# mini.net
KiCad netlist of a schematic drawn in Altium Designer
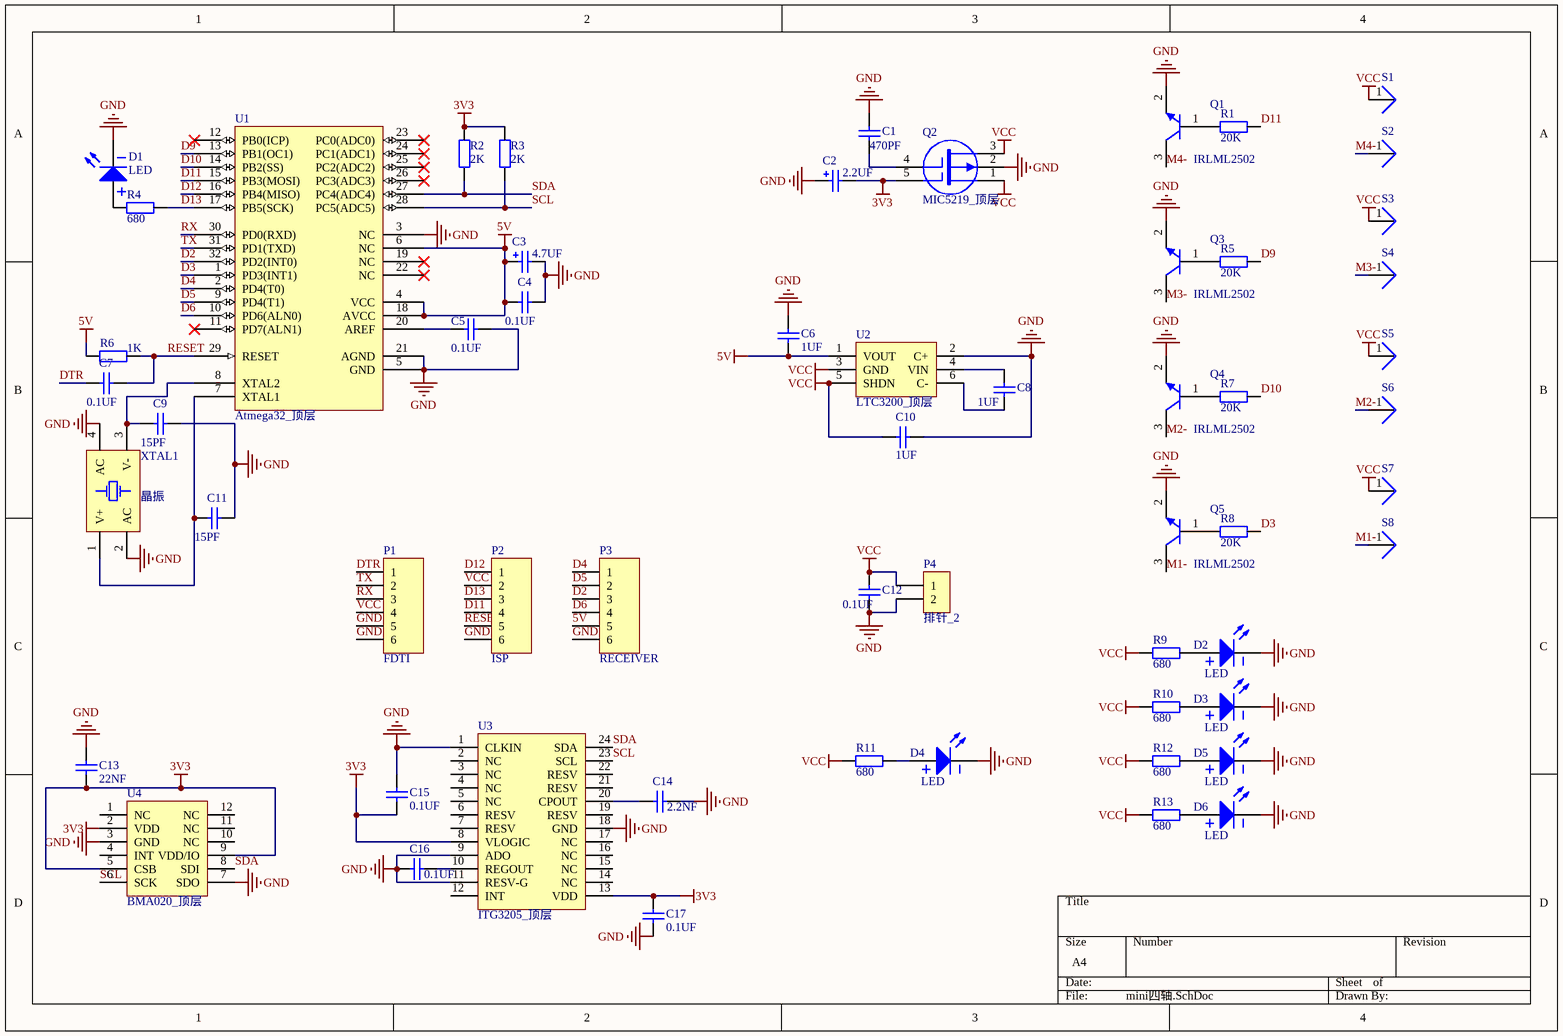
[diagram p0: mini四轴.SchDoc]

(export (version "E")
  (design (tool "Eeschema 10.0.6"))
  (components
    (comp (ref "C1")
      (value "470PF")
      (footprint "0805_顶层")
      (description "电容")
      (libsource (lib "贴片库") (part "电容_无极性_0805_顶层"))
    )
    (comp (ref "C2")
      (value "2.2UF")
      (footprint "A型电容")
      (description "电容_A型")
      (libsource (lib "贴片库") (part "电容_A型"))
    )
    (comp (ref "C3")
      (value "4.7UF")
      (footprint "A型电容")
      (description "电容_A型")
      (libsource (lib "贴片库") (part "电容_A型"))
    )
    (comp (ref "C4")
      (value "0.1UF")
      (footprint "0805_顶层")
      (description "电容")
      (libsource (lib "贴片库") (part "电容_无极性_0805_顶层"))
    )
    (comp (ref "C5")
      (value "0.1UF")
      (footprint "0805_顶层")
      (description "电容")
      (libsource (lib "贴片库") (part "电容_无极性_0805_顶层"))
    )
    (comp (ref "C6")
      (value "1UF")
      (footprint "0805_顶层")
      (description "电容")
      (libsource (lib "贴片库") (part "电容_无极性_0805_顶层"))
    )
    (comp (ref "C7")
      (value "0.1UF")
      (footprint "0805_顶层")
      (description "电容")
      (libsource (lib "贴片库") (part "电容_无极性_0805_顶层"))
    )
    (comp (ref "C8")
      (value "1UF")
      (footprint "0805_顶层")
      (description "电容")
      (libsource (lib "贴片库") (part "电容_无极性_0805_顶层"))
    )
    (comp (ref "C9")
      (value "15PF")
      (footprint "0805_顶层")
      (description "电容")
      (libsource (lib "贴片库") (part "电容_无极性_0805_顶层"))
    )
    (comp (ref "C10")
      (value "1UF")
      (footprint "0805_顶层")
      (description "电容")
      (libsource (lib "贴片库") (part "电容_无极性_0805_顶层"))
    )
    (comp (ref "C11")
      (value "15PF")
      (footprint "0805_顶层")
      (description "电容")
      (libsource (lib "贴片库") (part "电容_无极性_0805_顶层"))
    )
    (comp (ref "C12")
      (value "0.1UF")
      (footprint "0805_顶层")
      (description "电容")
      (libsource (lib "贴片库") (part "电容_无极性_0805_顶层"))
    )
    (comp (ref "C13")
      (value "22NF")
      (footprint "0805_顶层")
      (description "电容")
      (libsource (lib "贴片库") (part "电容_无极性_0805_顶层"))
    )
    (comp (ref "C14")
      (value "2.2NF")
      (footprint "0805_顶层")
      (description "电容")
      (libsource (lib "贴片库") (part "电容_无极性_0805_顶层"))
    )
    (comp (ref "C15")
      (value "0.1UF")
      (footprint "0805_顶层")
      (description "电容")
      (libsource (lib "贴片库") (part "电容_无极性_0805_顶层"))
    )
    (comp (ref "C16")
      (value "0.1UF")
      (footprint "0805_顶层")
      (description "电容")
      (libsource (lib "贴片库") (part "电容_无极性_0805_顶层"))
    )
    (comp (ref "C17")
      (value "0.1UF")
      (footprint "0805_顶层")
      (description "电容")
      (libsource (lib "贴片库") (part "电容_无极性_0805_顶层"))
    )
    (comp (ref "D1") (value "LED") (footprint "0805_顶层") (libsource (lib "贴片库") (part "LED_0805_顶层")))
    (comp (ref "D2") (value "LED") (footprint "0805_顶层") (libsource (lib "贴片库") (part "LED_0805_顶层")))
    (comp (ref "D3") (value "LED") (footprint "0805_顶层") (libsource (lib "贴片库") (part "LED_0805_顶层")))
    (comp (ref "D4") (value "LED") (footprint "0805_顶层") (libsource (lib "贴片库") (part "LED_0805_顶层")))
    (comp (ref "D5") (value "LED") (footprint "0805_顶层") (libsource (lib "贴片库") (part "LED_0805_顶层")))
    (comp (ref "D6") (value "LED") (footprint "0805_顶层") (libsource (lib "贴片库") (part "LED_0805_顶层")))
    (comp (ref "P1")
      (value "FDTI")
      (footprint "排针_6_2.54")
      (description "排针_6_2.54")
      (libsource (lib "贴片库") (part "排针_6_2.54"))
    )
    (comp (ref "P2")
      (value "ISP")
      (footprint "排针_6_2.54")
      (description "排针_6_2.54")
      (libsource (lib "贴片库") (part "排针_6_2.54"))
    )
    (comp (ref "P3")
      (value "RECEIVER")
      (footprint "排针_6_2.54")
      (description "排针_6_2.54")
      (libsource (lib "贴片库") (part "排针_6_2.54"))
    )
    (comp (ref "P4") (value "排针_2") (footprint "排针_2") (libsource (lib "贴片库") (part "排针_2")))
    (comp (ref "Q1")
      (value "IRLML2502")
      (footprint "IRLML2502_顶层")
      (libsource (lib "贴片库") (part "IRLML2502_顶层"))
    )
    (comp (ref "Q2")
      (value "MIC5219_顶层")
      (footprint "MIC5219_顶层")
      (description "MIC5219")
      (libsource (lib "贴片库") (part "MIC5219_顶层"))
    )
    (comp (ref "Q3")
      (value "IRLML2502")
      (footprint "IRLML2502_顶层")
      (libsource (lib "贴片库") (part "IRLML2502_顶层"))
    )
    (comp (ref "Q4")
      (value "IRLML2502")
      (footprint "IRLML2502_顶层")
      (libsource (lib "贴片库") (part "IRLML2502_顶层"))
    )
    (comp (ref "Q5")
      (value "IRLML2502")
      (footprint "IRLML2502_顶层")
      (libsource (lib "贴片库") (part "IRLML2502_顶层"))
    )
    (comp (ref "R1")
      (value "20K")
      (footprint "0805_顶层")
      (description "电阻")
      (libsource (lib "贴片库") (part "电阻_0805_顶层"))
    )
    (comp (ref "R2")
      (value "2K")
      (footprint "0805_顶层")
      (description "电阻")
      (libsource (lib "") (part "电阻_0805_顶层_1"))
    )
    (comp (ref "R3")
      (value "2K")
      (footprint "0805_顶层")
      (description "电阻")
      (libsource (lib "") (part "电阻_0805_顶层_1"))
    )
    (comp (ref "R4")
      (value "680")
      (footprint "0805_顶层")
      (description "电阻")
      (libsource (lib "贴片库") (part "电阻_0805_顶层"))
    )
    (comp (ref "R5")
      (value "20K")
      (footprint "0805_顶层")
      (description "电阻")
      (libsource (lib "贴片库") (part "电阻_0805_顶层"))
    )
    (comp (ref "R6")
      (value "1K")
      (footprint "0805_顶层")
      (description "电阻")
      (libsource (lib "贴片库") (part "电阻_0805_顶层"))
    )
    (comp (ref "R7")
      (value "20K")
      (footprint "0805_顶层")
      (description "电阻")
      (libsource (lib "贴片库") (part "电阻_0805_顶层"))
    )
    (comp (ref "R8")
      (value "20K")
      (footprint "0805_顶层")
      (description "电阻")
      (libsource (lib "贴片库") (part "电阻_0805_顶层"))
    )
    (comp (ref "R9")
      (value "680")
      (footprint "0805_顶层")
      (description "电阻")
      (libsource (lib "贴片库") (part "电阻_0805_顶层"))
    )
    (comp (ref "R10")
      (value "680")
      (footprint "0805_顶层")
      (description "电阻")
      (libsource (lib "贴片库") (part "电阻_0805_顶层"))
    )
    (comp (ref "R11")
      (value "680")
      (footprint "0805_顶层")
      (description "电阻")
      (libsource (lib "贴片库") (part "电阻_0805_顶层"))
    )
    (comp (ref "R12")
      (value "680")
      (footprint "0805_顶层")
      (description "电阻")
      (libsource (lib "贴片库") (part "电阻_0805_顶层"))
    )
    (comp (ref "R13")
      (value "680")
      (footprint "0805_顶层")
      (description "电阻")
      (libsource (lib "贴片库") (part "电阻_0805_顶层"))
    )
    (comp (ref "S1")
      (value "~")
      (footprint "焊盘_顶层")
      (description "焊盘")
      (libsource (lib "贴片库") (part "焊盘_顶层"))
    )
    (comp (ref "S2")
      (value "~")
      (footprint "焊盘_顶层")
      (description "焊盘")
      (libsource (lib "贴片库") (part "焊盘_顶层"))
    )
    (comp (ref "S3")
      (value "~")
      (footprint "焊盘_顶层")
      (description "焊盘")
      (libsource (lib "贴片库") (part "焊盘_顶层"))
    )
    (comp (ref "S4")
      (value "~")
      (footprint "焊盘_顶层")
      (description "焊盘")
      (libsource (lib "贴片库") (part "焊盘_顶层"))
    )
    (comp (ref "S5")
      (value "~")
      (footprint "焊盘_顶层")
      (description "焊盘")
      (libsource (lib "贴片库") (part "焊盘_顶层"))
    )
    (comp (ref "S6")
      (value "~")
      (footprint "焊盘_顶层")
      (description "焊盘")
      (libsource (lib "贴片库") (part "焊盘_顶层"))
    )
    (comp (ref "S7")
      (value "~")
      (footprint "焊盘_顶层")
      (description "焊盘")
      (libsource (lib "贴片库") (part "焊盘_顶层"))
    )
    (comp (ref "S8")
      (value "~")
      (footprint "焊盘_顶层")
      (description "焊盘")
      (libsource (lib "贴片库") (part "焊盘_顶层"))
    )
    (comp (ref "U1")
      (value "Atmega32_顶层")
      (footprint "Atmega32_顶层")
      (description "Atmega32")
      (libsource (lib "贴片库") (part "Atmega32_顶层"))
    )
    (comp (ref "U2")
      (value "LTC3200_顶层")
      (footprint "LTC3200_顶层")
      (description "LTC3200")
      (libsource (lib "贴片库") (part "LTC3200_顶层"))
    )
    (comp (ref "U3")
      (value "ITG3205_顶层")
      (footprint "ITG3205_顶层")
      (description "ITG3205")
      (libsource (lib "贴片库") (part "ITG3205_顶层"))
    )
    (comp (ref "U4")
      (value "BMA020_顶层")
      (footprint "BMA020_顶层")
      (description "BMA020")
      (libsource (lib "贴片库") (part "BMA020_顶层"))
    )
    (comp (ref "XTAL1") (value "晶振") (footprint "晶振_3225_顶层") (libsource (lib "贴片库") (part "晶振_3225_顶层")))
  )
  (nets
    (net (code "1") (name "/D2") (class "Default")
      (node (ref "P3") (pin "3") (pinfunction "3_3") (pintype "passive"))
      (node (ref "U1") (pin "32") (pinfunction "PD2(INT0)_32") (pintype "bidirectional"))
    )
    (net (code "2") (name "/D3") (class "Default")
      (node (ref "R8") (pin "1") (pinfunction "1_1") (pintype "passive"))
      (node (ref "U1") (pin "1") (pinfunction "PD3(INT1)_1") (pintype "bidirectional"))
    )
    (net (code "3") (name "/D4") (class "Default")
      (node (ref "P3") (pin "1") (pinfunction "1_1") (pintype "passive"))
      (node (ref "U1") (pin "2") (pinfunction "PD4(T0)_2") (pintype "bidirectional"))
    )
    (net (code "4") (name "/D5") (class "Default")
      (node (ref "P3") (pin "2") (pinfunction "2_2") (pintype "passive"))
      (node (ref "U1") (pin "9") (pinfunction "PD4(T1)_9") (pintype "bidirectional"))
    )
    (net (code "5") (name "/D6") (class "Default")
      (node (ref "P3") (pin "4") (pinfunction "4_4") (pintype "passive"))
      (node (ref "U1") (pin "10") (pinfunction "PD6(ALN0)_10") (pintype "bidirectional"))
    )
    (net (code "6") (name "/D9") (class "Default")
      (node (ref "R5") (pin "1") (pinfunction "1_1") (pintype "passive"))
      (node (ref "U1") (pin "13") (pinfunction "PB1(OC1)_13") (pintype "bidirectional"))
    )
    (net (code "7") (name "/D10") (class "Default")
      (node (ref "R7") (pin "1") (pinfunction "1_1") (pintype "passive"))
      (node (ref "U1") (pin "14") (pinfunction "PB2(SS)_14") (pintype "bidirectional"))
    )
    (net (code "8") (name "/D11") (class "Default")
      (node (ref "P2") (pin "4") (pinfunction "4_4") (pintype "passive"))
      (node (ref "R1") (pin "1") (pinfunction "1_1") (pintype "passive"))
      (node (ref "U1") (pin "15") (pinfunction "PB3(MOSI)_15") (pintype "bidirectional"))
    )
    (net (code "9") (name "/D12") (class "Default")
      (node (ref "P2") (pin "1") (pinfunction "1_1") (pintype "passive"))
      (node (ref "U1") (pin "16") (pinfunction "PB4(MISO)_16") (pintype "bidirectional"))
    )
    (net (code "10") (name "/D13") (class "Default")
      (node (ref "P2") (pin "3") (pinfunction "3_3") (pintype "passive"))
      (node (ref "R4") (pin "1") (pinfunction "1_1") (pintype "passive"))
      (node (ref "U1") (pin "17") (pinfunction "PB5(SCK)_17") (pintype "bidirectional"))
    )
    (net (code "11") (name "/DTR") (class "Default")
      (node (ref "C7") (pin "1") (pinfunction "1_1") (pintype "passive"))
      (node (ref "P1") (pin "1") (pinfunction "1_1") (pintype "passive"))
    )
    (net (code "12") (name "/M1-") (class "Default")
      (node (ref "Q5") (pin "3") (pinfunction "3_3") (pintype "passive"))
      (node (ref "S8") (pin "1") (pinfunction "1_1") (pintype "passive"))
    )
    (net (code "13") (name "/M2-") (class "Default")
      (node (ref "Q4") (pin "3") (pinfunction "3_3") (pintype "passive"))
      (node (ref "S6") (pin "1") (pinfunction "1_1") (pintype "passive"))
    )
    (net (code "14") (name "/M3-") (class "Default")
      (node (ref "Q3") (pin "3") (pinfunction "3_3") (pintype "passive"))
      (node (ref "S4") (pin "1") (pinfunction "1_1") (pintype "passive"))
    )
    (net (code "15") (name "/M4-") (class "Default")
      (node (ref "Q1") (pin "3") (pinfunction "3_3") (pintype "passive"))
      (node (ref "S2") (pin "1") (pinfunction "1_1") (pintype "passive"))
    )
    (net (code "16") (name "/RESET") (class "Default")
      (node (ref "C7") (pin "2") (pinfunction "2_2") (pintype "passive"))
      (node (ref "P2") (pin "5") (pinfunction "5_5") (pintype "passive"))
      (node (ref "R6") (pin "1") (pinfunction "1_1") (pintype "passive"))
      (node (ref "U1") (pin "29") (pinfunction "RESET_29") (pintype "input"))
    )
    (net (code "17") (name "/RX") (class "Default")
      (node (ref "P1") (pin "3") (pinfunction "3_3") (pintype "passive"))
      (node (ref "U1") (pin "30") (pinfunction "PD0(RXD)_30") (pintype "bidirectional"))
    )
    (net (code "18") (name "/SCL") (class "Default")
      (node (ref "R3") (pin "2") (pinfunction "2_2") (pintype "passive"))
      (node (ref "U1") (pin "28") (pinfunction "PC5(ADC5)_28") (pintype "bidirectional"))
      (node (ref "U3") (pin "23") (pinfunction "SCL_23") (pintype "passive"))
      (node (ref "U4") (pin "6") (pinfunction "SCK_6") (pintype "passive"))
    )
    (net (code "19") (name "/SDA") (class "Default")
      (node (ref "R2") (pin "2") (pinfunction "2_2") (pintype "passive"))
      (node (ref "U1") (pin "27") (pinfunction "PC4(ADC4)_27") (pintype "bidirectional"))
      (node (ref "U3") (pin "24") (pinfunction "SDA_24") (pintype "passive"))
      (node (ref "U4") (pin "8") (pinfunction "SDI_8") (pintype "passive"))
    )
    (net (code "20") (name "/TX") (class "Default")
      (node (ref "P1") (pin "2") (pinfunction "2_2") (pintype "passive"))
      (node (ref "U1") (pin "31") (pinfunction "PD1(TXD)_31") (pintype "bidirectional"))
    )
    (net (code "21") (name "3V3") (class "Default")
      (node (ref "C13") (pin "1") (pinfunction "1_1") (pintype "passive"))
      (node (ref "C15") (pin "1") (pinfunction "1_1") (pintype "passive"))
      (node (ref "C17") (pin "2") (pinfunction "2_2") (pintype "passive"))
      (node (ref "C2") (pin "2") (pinfunction "2_2") (pintype "passive"))
      (node (ref "Q2") (pin "5") (pinfunction "5_5") (pintype "passive"))
      (node (ref "R2") (pin "1") (pinfunction "1_1") (pintype "passive"))
      (node (ref "R3") (pin "1") (pinfunction "1_1") (pintype "passive"))
      (node (ref "U3") (pin "13") (pinfunction "VDD_13") (pintype "passive"))
      (node (ref "U3") (pin "8") (pinfunction "VLOGIC_8") (pintype "passive"))
      (node (ref "U4") (pin "2") (pinfunction "VDD_2") (pintype "passive"))
      (node (ref "U4") (pin "5") (pinfunction "CSB_5") (pintype "passive"))
      (node (ref "U4") (pin "9") (pinfunction "VDD/IO_9") (pintype "passive"))
    )
    (net (code "22") (name "5V") (class "Default")
      (node (ref "C3") (pin "1") (pinfunction "1_1") (pintype "passive"))
      (node (ref "C4") (pin "1") (pinfunction "1_1") (pintype "passive"))
      (node (ref "C6") (pin "1") (pinfunction "1_1") (pintype "passive"))
      (node (ref "P3") (pin "5") (pinfunction "5_5") (pintype "passive"))
      (node (ref "R6") (pin "2") (pinfunction "2_2") (pintype "passive"))
      (node (ref "U1") (pin "18") (pinfunction "AVCC_18") (pintype "passive"))
      (node (ref "U1") (pin "4") (pinfunction "VCC_4") (pintype "passive"))
      (node (ref "U1") (pin "6") (pinfunction "NC_6") (pintype "passive"))
      (node (ref "U2") (pin "1") (pinfunction "VOUT_1") (pintype "passive"))
    )
    (net (code "23") (name "GND") (class "Default")
      (node (ref "C1") (pin "2") (pinfunction "2_2") (pintype "passive"))
      (node (ref "C10") (pin "1") (pinfunction "1_1") (pintype "passive"))
      (node (ref "C11") (pin "2") (pinfunction "2_2") (pintype "passive"))
      (node (ref "C12") (pin "1") (pinfunction "1_1") (pintype "passive"))
      (node (ref "C13") (pin "2") (pinfunction "2_2") (pintype "passive"))
      (node (ref "C14") (pin "2") (pinfunction "2_2") (pintype "passive"))
      (node (ref "C15") (pin "2") (pinfunction "2_2") (pintype "passive"))
      (node (ref "C16") (pin "1") (pinfunction "1_1") (pintype "passive"))
      (node (ref "C17") (pin "1") (pinfunction "1_1") (pintype "passive"))
      (node (ref "C2") (pin "1") (pinfunction "1_1") (pintype "passive"))
      (node (ref "C3") (pin "2") (pinfunction "2_2") (pintype "passive"))
      (node (ref "C4") (pin "2") (pinfunction "2_2") (pintype "passive"))
      (node (ref "C5") (pin "2") (pinfunction "2_2") (pintype "passive"))
      (node (ref "C6") (pin "2") (pinfunction "2_2") (pintype "passive"))
      (node (ref "C9") (pin "2") (pinfunction "2_2") (pintype "passive"))
      (node (ref "D1") (pin "2") (pinfunction "K_2") (pintype "passive"))
      (node (ref "D2") (pin "2") (pinfunction "K_2") (pintype "passive"))
      (node (ref "D3") (pin "2") (pinfunction "K_2") (pintype "passive"))
      (node (ref "D4") (pin "2") (pinfunction "K_2") (pintype "passive"))
      (node (ref "D5") (pin "2") (pinfunction "K_2") (pintype "passive"))
      (node (ref "D6") (pin "2") (pinfunction "K_2") (pintype "passive"))
      (node (ref "P1") (pin "5") (pinfunction "5_5") (pintype "passive"))
      (node (ref "P1") (pin "6") (pinfunction "6_6") (pintype "passive"))
      (node (ref "P2") (pin "6") (pinfunction "6_6") (pintype "passive"))
      (node (ref "P3") (pin "6") (pinfunction "6_6") (pintype "passive"))
      (node (ref "P4") (pin "2") (pinfunction "2_2") (pintype "passive"))
      (node (ref "Q1") (pin "2") (pinfunction "2_2") (pintype "passive"))
      (node (ref "Q2") (pin "2") (pinfunction "2_2") (pintype "passive"))
      (node (ref "Q3") (pin "2") (pinfunction "2_2") (pintype "passive"))
      (node (ref "Q4") (pin "2") (pinfunction "2_2") (pintype "passive"))
      (node (ref "Q5") (pin "2") (pinfunction "2_2") (pintype "passive"))
      (node (ref "U1") (pin "21") (pinfunction "AGND_21") (pintype "passive"))
      (node (ref "U1") (pin "3") (pinfunction "NC_3") (pintype "passive"))
      (node (ref "U1") (pin "5") (pinfunction "GND_5") (pintype "passive"))
      (node (ref "U2") (pin "2") (pinfunction "C+_2") (pintype "passive"))
      (node (ref "U3") (pin "1") (pinfunction "CLKIN_1") (pintype "passive"))
      (node (ref "U3") (pin "11") (pinfunction "RESV-G_11") (pintype "passive"))
      (node (ref "U3") (pin "18") (pinfunction "GND_18") (pintype "passive"))
      (node (ref "U3") (pin "9") (pinfunction "ADO_9") (pintype "passive"))
      (node (ref "U4") (pin "3") (pinfunction "GND_3") (pintype "passive"))
      (node (ref "U4") (pin "7") (pinfunction "SDO_7") (pintype "passive"))
      (node (ref "XTAL1") (pin "2") (pinfunction "AC_2") (pintype "passive"))
      (node (ref "XTAL1") (pin "4") (pinfunction "AC_4") (pintype "passive"))
    )
    (net (code "24") (name "Net-(C1-Pad1)") (class "Default")
      (node (ref "C1") (pin "1") (pinfunction "1_1") (pintype "passive"))
      (node (ref "Q2") (pin "4") (pinfunction "4_4") (pintype "passive"))
    )
    (net (code "25") (name "Net-(D1-A)") (class "Default")
      (node (ref "D1") (pin "1") (pinfunction "A_1") (pintype "passive"))
      (node (ref "R4") (pin "2") (pinfunction "2_2") (pintype "passive"))
    )
    (net (code "26") (name "Net-(D2-A)") (class "Default")
      (node (ref "D2") (pin "1") (pinfunction "A_1") (pintype "passive"))
      (node (ref "R9") (pin "1") (pinfunction "1_1") (pintype "passive"))
    )
    (net (code "27") (name "Net-(D3-A)") (class "Default")
      (node (ref "D3") (pin "1") (pinfunction "A_1") (pintype "passive"))
      (node (ref "R10") (pin "1") (pinfunction "1_1") (pintype "passive"))
    )
    (net (code "28") (name "Net-(D4-A)") (class "Default")
      (node (ref "D4") (pin "1") (pinfunction "A_1") (pintype "passive"))
      (node (ref "R11") (pin "1") (pinfunction "1_1") (pintype "passive"))
    )
    (net (code "29") (name "Net-(D5-A)") (class "Default")
      (node (ref "D5") (pin "1") (pinfunction "A_1") (pintype "passive"))
      (node (ref "R12") (pin "1") (pinfunction "1_1") (pintype "passive"))
    )
    (net (code "30") (name "Net-(D6-A)") (class "Default")
      (node (ref "D6") (pin "1") (pinfunction "A_1") (pintype "passive"))
      (node (ref "R13") (pin "1") (pinfunction "1_1") (pintype "passive"))
    )
    (net (code "31") (name "Net-(Q1-Pad1)") (class "Default")
      (node (ref "Q1") (pin "1") (pinfunction "1_1") (pintype "passive"))
      (node (ref "R1") (pin "2") (pinfunction "2_2") (pintype "passive"))
    )
    (net (code "32") (name "Net-(Q3-Pad1)") (class "Default")
      (node (ref "Q3") (pin "1") (pinfunction "1_1") (pintype "passive"))
      (node (ref "R5") (pin "2") (pinfunction "2_2") (pintype "passive"))
    )
    (net (code "33") (name "Net-(Q4-Pad1)") (class "Default")
      (node (ref "Q4") (pin "1") (pinfunction "1_1") (pintype "passive"))
      (node (ref "R7") (pin "2") (pinfunction "2_2") (pintype "passive"))
    )
    (net (code "34") (name "Net-(Q5-Pad1)") (class "Default")
      (node (ref "Q5") (pin "1") (pinfunction "1_1") (pintype "passive"))
      (node (ref "R8") (pin "2") (pinfunction "2_2") (pintype "passive"))
    )
    (net (code "35") (name "Net-(U1-AREF)") (class "Default")
      (node (ref "C5") (pin "1") (pinfunction "1_1") (pintype "passive"))
      (node (ref "U1") (pin "20") (pinfunction "AREF_20") (pintype "passive"))
    )
    (net (code "36") (name "Net-(U1-XTAL1)") (class "Default")
      (node (ref "C11") (pin "1") (pinfunction "1_1") (pintype "passive"))
      (node (ref "U1") (pin "7") (pinfunction "XTAL1_7") (pintype "passive"))
      (node (ref "XTAL1") (pin "1") (pinfunction "V+_1") (pintype "passive"))
    )
    (net (code "37") (name "Net-(U1-XTAL2)") (class "Default")
      (node (ref "C9") (pin "1") (pinfunction "1_1") (pintype "passive"))
      (node (ref "U1") (pin "8") (pinfunction "XTAL2_8") (pintype "passive"))
      (node (ref "XTAL1") (pin "3") (pinfunction "V-_3") (pintype "passive"))
    )
    (net (code "38") (name "Net-(U2-C-)") (class "Default")
      (node (ref "C8") (pin "2") (pinfunction "2_2") (pintype "passive"))
      (node (ref "U2") (pin "6") (pinfunction "C-_6") (pintype "passive"))
    )
    (net (code "39") (name "Net-(U2-VIN)") (class "Default")
      (node (ref "C8") (pin "1") (pinfunction "1_1") (pintype "passive"))
      (node (ref "U2") (pin "4") (pinfunction "VIN_4") (pintype "passive"))
    )
    (net (code "40") (name "Net-(U3-CPOUT)") (class "Default")
      (node (ref "C14") (pin "1") (pinfunction "1_1") (pintype "passive"))
      (node (ref "U3") (pin "20") (pinfunction "CPOUT_20") (pintype "passive"))
    )
    (net (code "41") (name "Net-(U3-REGOUT)") (class "Default")
      (node (ref "C16") (pin "2") (pinfunction "2_2") (pintype "passive"))
      (node (ref "U3") (pin "10") (pinfunction "REGOUT_10") (pintype "passive"))
    )
    (net (code "42") (name "VCC") (class "Default")
      (node (ref "C10") (pin "2") (pinfunction "2_2") (pintype "passive"))
      (node (ref "C12") (pin "2") (pinfunction "2_2") (pintype "passive"))
      (node (ref "P1") (pin "4") (pinfunction "4_4") (pintype "passive"))
      (node (ref "P2") (pin "2") (pinfunction "2_2") (pintype "passive"))
      (node (ref "P4") (pin "1") (pinfunction "1_1") (pintype "passive"))
      (node (ref "Q2") (pin "1") (pinfunction "1_1") (pintype "passive"))
      (node (ref "Q2") (pin "3") (pinfunction "3_3") (pintype "passive"))
      (node (ref "R10") (pin "2") (pinfunction "2_2") (pintype "passive"))
      (node (ref "R11") (pin "2") (pinfunction "2_2") (pintype "passive"))
      (node (ref "R12") (pin "2") (pinfunction "2_2") (pintype "passive"))
      (node (ref "R13") (pin "2") (pinfunction "2_2") (pintype "passive"))
      (node (ref "R9") (pin "2") (pinfunction "2_2") (pintype "passive"))
      (node (ref "S1") (pin "1") (pinfunction "1_1") (pintype "passive"))
      (node (ref "S3") (pin "1") (pinfunction "1_1") (pintype "passive"))
      (node (ref "S5") (pin "1") (pinfunction "1_1") (pintype "passive"))
      (node (ref "S7") (pin "1") (pinfunction "1_1") (pintype "passive"))
      (node (ref "U2") (pin "3") (pinfunction "GND_3") (pintype "passive"))
      (node (ref "U2") (pin "5") (pinfunction "SHDN_5") (pintype "passive"))
    )
    (net (code "43") (name "unconnected-(U1-NC-Pad19)") (class "Default")
      (node (ref "U1") (pin "19") (pinfunction "NC_19") (pintype "passive+no_connect"))
    )
    (net (code "44") (name "unconnected-(U1-NC-Pad22)") (class "Default")
      (node (ref "U1") (pin "22") (pinfunction "NC_22") (pintype "passive+no_connect"))
    )
    (net (code "45") (name "unconnected-(U1-PB0(ICP)-Pad12)") (class "Default")
      (node (ref "U1") (pin "12") (pinfunction "PB0(ICP)_12") (pintype "bidirectional+no_connect"))
    )
    (net (code "46") (name "unconnected-(U1-PC0(ADC0)-Pad23)") (class "Default")
      (node (ref "U1") (pin "23") (pinfunction "PC0(ADC0)_23") (pintype "bidirectional+no_connect"))
    )
    (net (code "47") (name "unconnected-(U1-PC1(ADC1)-Pad24)") (class "Default")
      (node (ref "U1") (pin "24") (pinfunction "PC1(ADC1)_24") (pintype "bidirectional+no_connect"))
    )
    (net (code "48") (name "unconnected-(U1-PC2(ADC2)-Pad25)") (class "Default")
      (node (ref "U1") (pin "25") (pinfunction "PC2(ADC2)_25") (pintype "bidirectional+no_connect"))
    )
    (net (code "49") (name "unconnected-(U1-PC3(ADC3)-Pad26)") (class "Default")
      (node (ref "U1") (pin "26") (pinfunction "PC3(ADC3)_26") (pintype "bidirectional+no_connect"))
    )
    (net (code "50") (name "unconnected-(U1-PD7(ALN1)-Pad11)") (class "Default")
      (node (ref "U1") (pin "11") (pinfunction "PD7(ALN1)_11") (pintype "bidirectional+no_connect"))
    )
    (net (code "51") (name "unconnected-(U3-INT-Pad12)") (class "Default")
      (node (ref "U3") (pin "12") (pinfunction "INT_12") (pintype "passive"))
    )
    (net (code "52") (name "unconnected-(U3-NC-Pad2)") (class "Default")
      (node (ref "U3") (pin "2") (pinfunction "NC_2") (pintype "passive"))
    )
    (net (code "53") (name "unconnected-(U3-NC-Pad3)") (class "Default")
      (node (ref "U3") (pin "3") (pinfunction "NC_3") (pintype "passive"))
    )
    (net (code "54") (name "unconnected-(U3-NC-Pad4)") (class "Default")
      (node (ref "U3") (pin "4") (pinfunction "NC_4") (pintype "passive"))
    )
    (net (code "55") (name "unconnected-(U3-NC-Pad5)") (class "Default")
      (node (ref "U3") (pin "5") (pinfunction "NC_5") (pintype "passive"))
    )
    (net (code "56") (name "unconnected-(U3-NC-Pad14)") (class "Default")
      (node (ref "U3") (pin "14") (pinfunction "NC_14") (pintype "passive"))
    )
    (net (code "57") (name "unconnected-(U3-NC-Pad15)") (class "Default")
      (node (ref "U3") (pin "15") (pinfunction "NC_15") (pintype "passive"))
    )
    (net (code "58") (name "unconnected-(U3-NC-Pad16)") (class "Default")
      (node (ref "U3") (pin "16") (pinfunction "NC_16") (pintype "passive"))
    )
    (net (code "59") (name "unconnected-(U3-NC-Pad17)") (class "Default")
      (node (ref "U3") (pin "17") (pinfunction "NC_17") (pintype "passive"))
    )
    (net (code "60") (name "unconnected-(U3-RESV-Pad6)") (class "Default")
      (node (ref "U3") (pin "6") (pinfunction "RESV_6") (pintype "passive"))
    )
    (net (code "61") (name "unconnected-(U3-RESV-Pad7)") (class "Default")
      (node (ref "U3") (pin "7") (pinfunction "RESV_7") (pintype "passive"))
    )
    (net (code "62") (name "unconnected-(U3-RESV-Pad19)") (class "Default")
      (node (ref "U3") (pin "19") (pinfunction "RESV_19") (pintype "passive"))
    )
    (net (code "63") (name "unconnected-(U3-RESV-Pad21)") (class "Default")
      (node (ref "U3") (pin "21") (pinfunction "RESV_21") (pintype "passive"))
    )
    (net (code "64") (name "unconnected-(U3-RESV-Pad22)") (class "Default")
      (node (ref "U3") (pin "22") (pinfunction "RESV_22") (pintype "passive"))
    )
    (net (code "65") (name "unconnected-(U4-INT-Pad4)") (class "Default")
      (node (ref "U4") (pin "4") (pinfunction "INT_4") (pintype "passive"))
    )
    (net (code "66") (name "unconnected-(U4-NC-Pad1)") (class "Default")
      (node (ref "U4") (pin "1") (pinfunction "NC_1") (pintype "passive"))
    )
    (net (code "67") (name "unconnected-(U4-NC-Pad10)") (class "Default")
      (node (ref "U4") (pin "10") (pinfunction "NC_10") (pintype "passive"))
    )
    (net (code "68") (name "unconnected-(U4-NC-Pad11)") (class "Default")
      (node (ref "U4") (pin "11") (pinfunction "NC_11") (pintype "passive"))
    )
    (net (code "69") (name "unconnected-(U4-NC-Pad12)") (class "Default")
      (node (ref "U4") (pin "12") (pinfunction "NC_12") (pintype "passive"))
    )
  )
)
